# rapidshark-dart-detector-mk-1_0.net
KiCad netlist of a schematic drawn in EAGLE
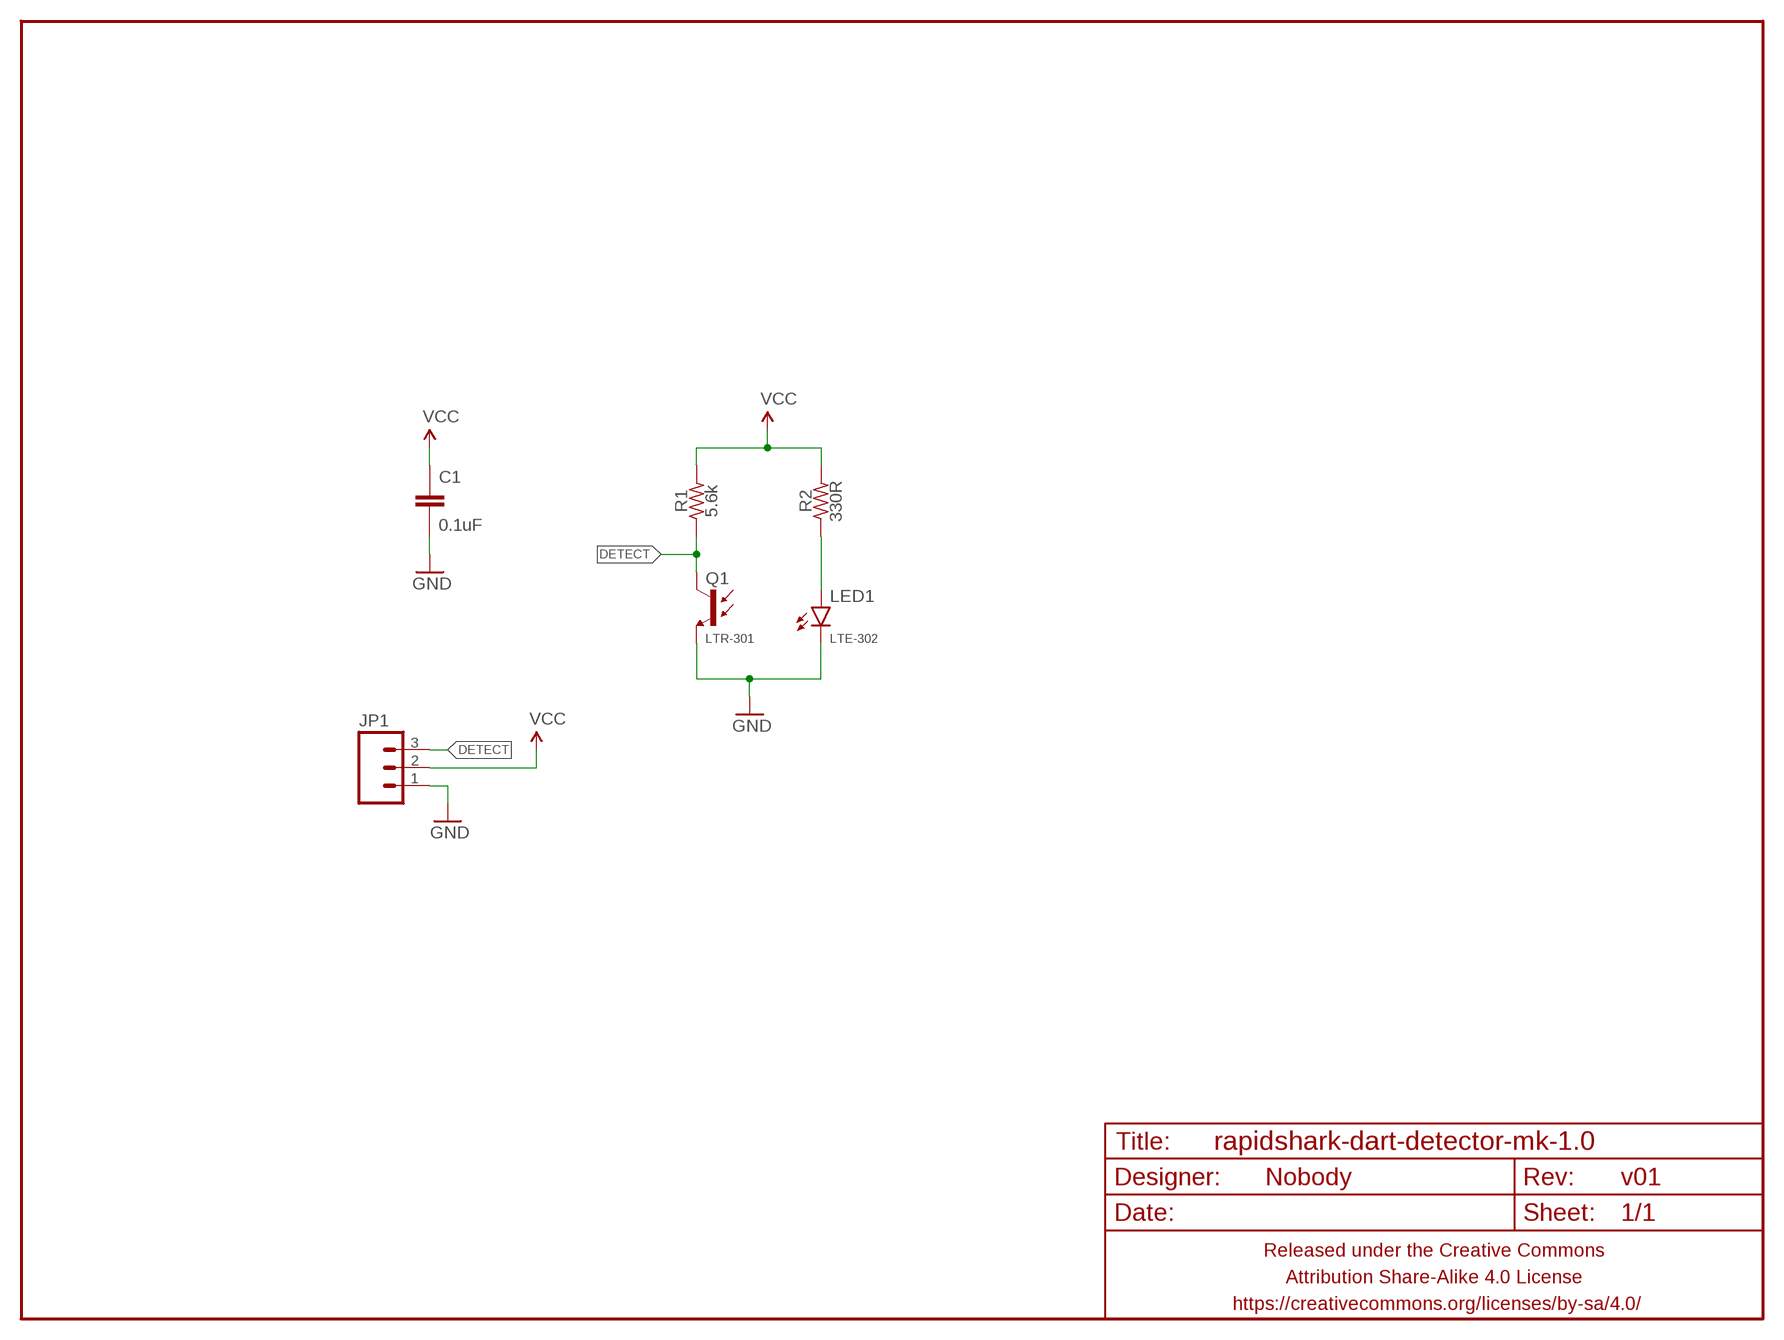
[diagram p0: schematic, sheet 1]

(export (version "E")
  (design (tool "Eeschema 10.0.6"))
  (components
    (comp (ref "C1")
      (value "0.1uF")
      (footprint "eagle-import:C0805")
      (libsource (lib "eagle-import") (part "CAPACITOR-CERAMICC0805"))
    )
    (comp (ref "FRAME1")
      (value "FRAME-LETTERNO_PACKAGE")
      (footprint "eagle-import:DUMMY")
      (fields (field (name "DESIGNER") "Nobody"))
      (libsource (lib "eagle-import") (part "FRAME-LETTERNO_PACKAGE"))
    )
    (comp (ref "JP1")
      (value "M03JST-PTH")
      (footprint "eagle-import:JST-3-PH-RA-PTH")
      (libsource (lib "eagle-import") (part "M03JST-PTH"))
    )
    (comp (ref "LED1")
      (value "LTE-302")
      (footprint "eagle-import:LED-2.54MM")
      (libsource (lib "eagle-import") (part "LED-VALUEIR-LED"))
    )
    (comp (ref "Q1")
      (value "LTR-301")
      (footprint "eagle-import:LED-2.54MM")
      (libsource (lib "eagle-import") (part "PHOTOTRANSISTOR2.54MM"))
    )
    (comp (ref "R1")
      (value "5.6k")
      (footprint "eagle-import:R0805")
      (libsource (lib "eagle-import") (part "RESISTORR0805"))
    )
    (comp (ref "R2")
      (value "330R")
      (footprint "eagle-import:R0805")
      (libsource (lib "eagle-import") (part "RESISTORR0805"))
    )
  )
  (nets
    (net (code "1") (name "DETECT") (class "Default")
      (node (ref "JP1") (pin "3") (pinfunction "3_3") (pintype "passive"))
      (node (ref "Q1") (pin "A") (pinfunction "C_A") (pintype "bidirectional"))
      (node (ref "R1") (pin "1") (pinfunction "1_1") (pintype "passive"))
    )
    (net (code "2") (name "GND") (class "Default")
      (node (ref "C1") (pin "2") (pinfunction "2_2") (pintype "passive"))
      (node (ref "JP1") (pin "1") (pinfunction "1_1") (pintype "passive"))
      (node (ref "LED1") (pin "K") (pinfunction "C_K") (pintype "passive"))
      (node (ref "Q1") (pin "K") (pinfunction "E_K") (pintype "bidirectional"))
    )
    (net (code "3") (name "Net-(LED1-PadA)") (class "Default")
      (node (ref "LED1") (pin "A") (pinfunction "A_A") (pintype "passive"))
      (node (ref "R2") (pin "1") (pinfunction "1_1") (pintype "passive"))
    )
    (net (code "4") (name "VCC") (class "Default")
      (node (ref "C1") (pin "1") (pinfunction "1_1") (pintype "passive"))
      (node (ref "JP1") (pin "2") (pinfunction "2_2") (pintype "passive"))
      (node (ref "R1") (pin "2") (pinfunction "2_2") (pintype "passive"))
      (node (ref "R2") (pin "2") (pinfunction "2_2") (pintype "passive"))
    )
  )
)
